# baseboardV0_1Part1.net
KiCad netlist of a schematic drawn in Altium Designer
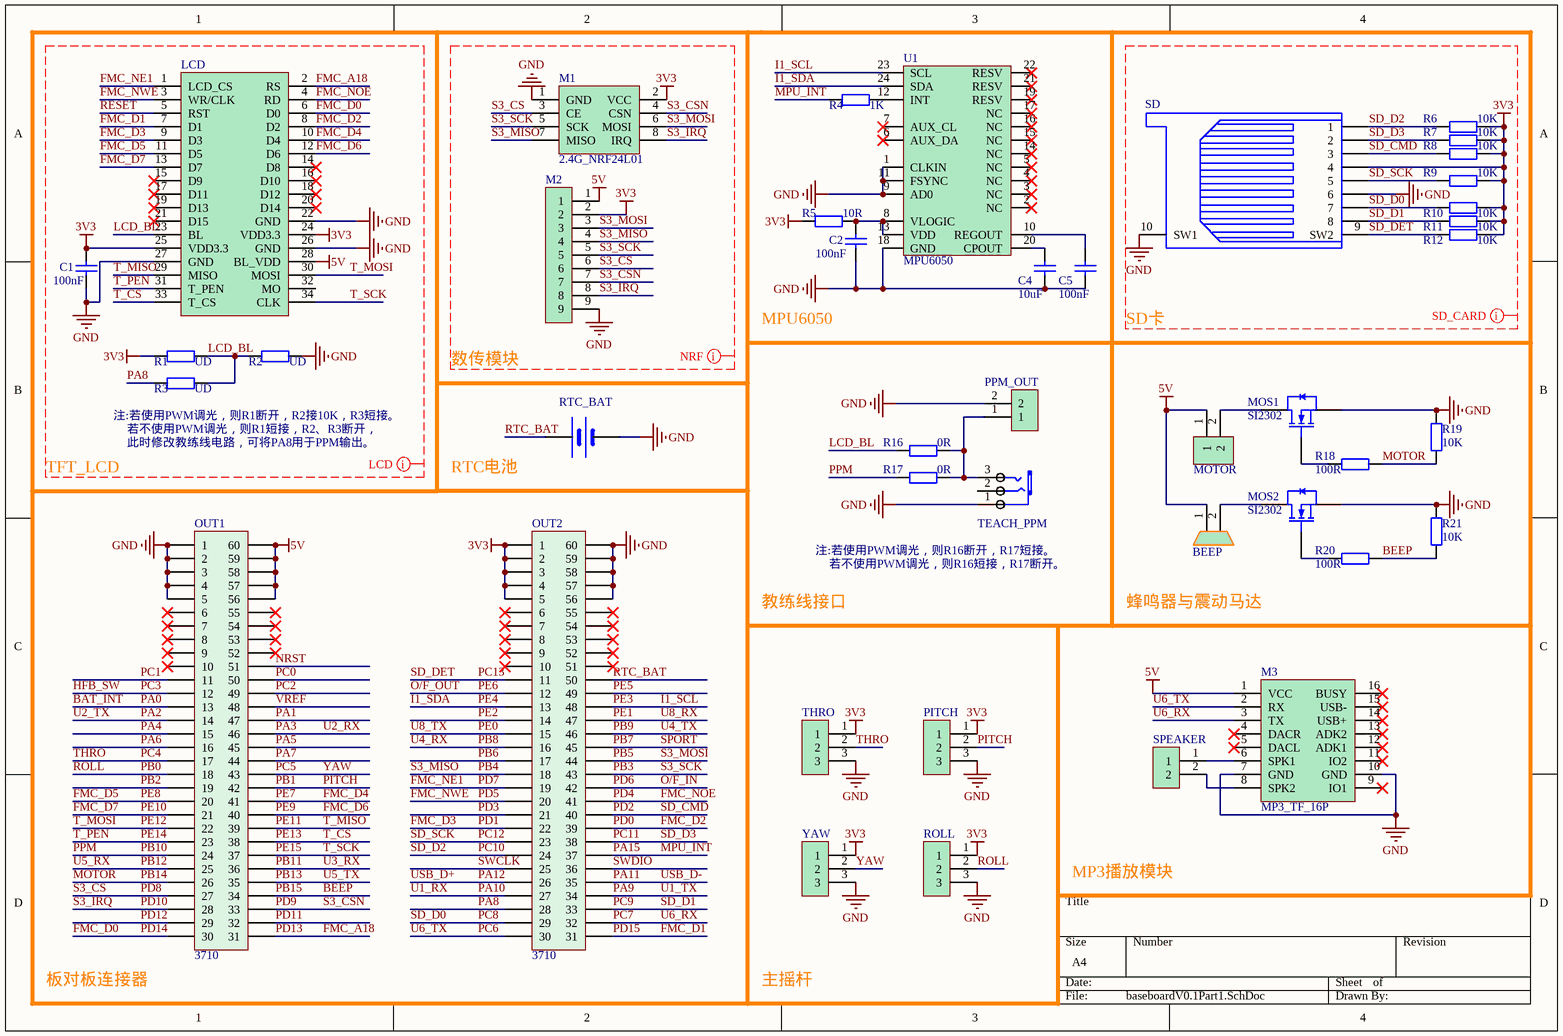
[diagram p0: baseboardV0.1Part1.SchDoc]

(export (version "E")
  (design (tool "Eeschema 10.0.6"))
  (components
    (comp (ref "BEEP")
      (value "BEEP_5020_SMT")
      (footprint "BEEP_5020_SMT")
      (libsource (lib "MT_Device") (part "BEEP_5020_SMT"))
    )
    (comp (ref "C1") (value "100nF") (footprint "0603_C") (libsource (lib "MT_Device") (part "0603_CAP")))
    (comp (ref "C2") (value "100nF") (footprint "0603_C") (libsource (lib "MT_Device") (part "0603_CAP")))
    (comp (ref "C4") (value "10uF") (footprint "0603_C") (libsource (lib "MT_Device") (part "0603_CAP")))
    (comp (ref "C5") (value "100nF") (footprint "0603_C") (libsource (lib "MT_Device") (part "0603_CAP")))
    (comp (ref "LCD")
      (value "LCD_3.5_480*320_SMT")
      (footprint "LCD_3.5_480*320_SMT")
      (libsource (lib "MT_Module") (part "LCD_3.5_480*320_SMT"))
    )
    (comp (ref "M1")
      (value "2.4G_NRF24L01")
      (footprint "2.4G_NRF24L01")
      (libsource (lib "MT_Module") (part "2.4G_NRF24L01"))
    )
    (comp (ref "M2")
      (value "SH1.25mm_9P")
      (footprint "SH1.25MM_9P")
      (libsource (lib "MT_Connector") (part "SH1.25mm_9P"))
    )
    (comp (ref "M3")
      (value "MP3_TF_16P")
      (footprint "MP3_TF_16P")
      (libsource (lib "MT_Module") (part "MP3_TF_16P"))
    )
    (comp (ref "MOS1")
      (value "SI2302")
      (footprint "SOT23")
      (libsource (lib "MT_Device") (part "MOSN_SI2302_SOT23"))
    )
    (comp (ref "MOS2")
      (value "SI2302")
      (footprint "SOT23")
      (libsource (lib "MT_Device") (part "MOSN_SI2302_SOT23"))
    )
    (comp (ref "MOTOR")
      (value "SH1.25mm_2P")
      (footprint "SH1.25mm_2P")
      (libsource (lib "") (part "SH1.25mm_2P_1"))
    )
    (comp (ref "OUT1")
      (value "3710")
      (footprint "3710F060046G3FT01")
      (libsource (lib "MT_Connector") (part "3710F_30*2pin"))
    )
    (comp (ref "OUT2")
      (value "3710")
      (footprint "3710F060046G3FT01")
      (libsource (lib "MT_Connector") (part "3710F_30*2pin"))
    )
    (comp (ref "PITCH")
      (value "pitch")
      (footprint "SH1.25mm_3P")
      (libsource (lib "MT_Connector") (part "SH1.25mm_3P"))
    )
    (comp (ref "PPM_OUT")
      (value "SH1.25mm_2P")
      (footprint "SH1.25mm_2P")
      (libsource (lib "") (part "SH1.25mm_2P_2"))
    )
    (comp (ref "R1") (value "UD") (footprint "0603_R") (libsource (lib "") (part "0603_RES_1")))
    (comp (ref "R2") (value "UD") (footprint "0603_R") (libsource (lib "") (part "0603_RES_1")))
    (comp (ref "R3") (value "UD") (footprint "0603_R") (libsource (lib "") (part "0603_RES_1")))
    (comp (ref "R4") (value "1K") (footprint "0603_R") (libsource (lib "") (part "0603_RES_1")))
    (comp (ref "R5") (value "10R") (footprint "0603_R") (libsource (lib "") (part "0603_RES_1")))
    (comp (ref "R6") (value "10K") (footprint "0603_R") (libsource (lib "") (part "0603_RES_1")))
    (comp (ref "R7") (value "10K") (footprint "0603_R") (libsource (lib "") (part "0603_RES_1")))
    (comp (ref "R8") (value "10K") (footprint "0603_R") (libsource (lib "") (part "0603_RES_1")))
    (comp (ref "R9") (value "10K") (footprint "0603_R") (libsource (lib "") (part "0603_RES_1")))
    (comp (ref "R10") (value "10K") (footprint "0603_R") (libsource (lib "") (part "0603_RES_1")))
    (comp (ref "R11") (value "10K") (footprint "0603_R") (libsource (lib "") (part "0603_RES_1")))
    (comp (ref "R12") (value "10K") (footprint "0603_R") (libsource (lib "") (part "0603_RES_1")))
    (comp (ref "R16") (value "0R") (footprint "0603_R") (libsource (lib "MT_Device") (part "0603_RES")))
    (comp (ref "R17") (value "0R") (footprint "0603_R") (libsource (lib "MT_Device") (part "0603_RES")))
    (comp (ref "R18") (value "100R") (footprint "0603_R") (libsource (lib "") (part "0603_RES_1")))
    (comp (ref "R19") (value "10K") (footprint "0603_R") (libsource (lib "") (part "0603_RES_2")))
    (comp (ref "R20") (value "100R") (footprint "0603_R") (libsource (lib "") (part "0603_RES_1")))
    (comp (ref "R21") (value "10K") (footprint "0603_R") (libsource (lib "") (part "0603_RES_2")))
    (comp (ref "ROLL")
      (value "roll")
      (footprint "SH1.25mm_3P")
      (libsource (lib "MT_Connector") (part "SH1.25mm_3P"))
    )
    (comp (ref "RTC_BAT")
      (value "CR1220_BATTERY")
      (footprint "CR1220_BATTERY")
      (libsource (lib "MT_Device") (part "CR1220_BATTERY"))
    )
    (comp (ref "SD") (value "TF_Card") (footprint "TF_card") (libsource (lib "MT_Device") (part "TF_Card")))
    (comp (ref "SPEAKER")
      (value "SH1.25mm_2P")
      (footprint "SH1.25mm_2P")
      (libsource (lib "MT_Connector") (part "SH1.25mm_2P"))
    )
    (comp (ref "TEACH_PPM")
      (value "AUDIO_PJ313D")
      (footprint "AUDIO_PJ313D")
      (libsource (lib "MT_Device") (part "AUDIO_PJ313D"))
    )
    (comp (ref "THRO")
      (value "thro")
      (footprint "SH1.25mm_3P")
      (libsource (lib "MT_Connector") (part "SH1.25mm_3P"))
    )
    (comp (ref "U1") (value "MPU6050") (footprint "QFN24") (libsource (lib "MT_Chip") (part "MPU6050")))
    (comp (ref "YAW")
      (value "yaw")
      (footprint "SH1.25mm_3P")
      (libsource (lib "MT_Connector") (part "SH1.25mm_3P"))
    )
  )
  (nets
    (net (code "1") (name "/BAT_INT") (class "Default")
      (node (ref "OUT1") (pin "13") (pinfunction "13_13") (pintype "passive"))
    )
    (net (code "2") (name "/BEEP") (class "Default")
      (node (ref "OUT1") (pin "34") (pinfunction "34_34") (pintype "passive"))
      (node (ref "R20") (pin "2") (pinfunction "2_2") (pintype "passive"))
      (node (ref "R21") (pin "1") (pinfunction "1_1") (pintype "passive"))
    )
    (net (code "3") (name "/FMC_A18") (class "Default")
      (node (ref "LCD") (pin "2") (pinfunction "RS_2") (pintype "passive"))
      (node (ref "OUT1") (pin "31") (pinfunction "31_31") (pintype "passive"))
    )
    (net (code "4") (name "/FMC_D0") (class "Default")
      (node (ref "LCD") (pin "6") (pinfunction "D0_6") (pintype "passive"))
      (node (ref "OUT1") (pin "30") (pinfunction "30_30") (pintype "passive"))
    )
    (net (code "5") (name "/FMC_D1") (class "Default")
      (node (ref "LCD") (pin "7") (pinfunction "D1_7") (pintype "passive"))
      (node (ref "OUT2") (pin "31") (pinfunction "31_31") (pintype "passive"))
    )
    (net (code "6") (name "/FMC_D2") (class "Default")
      (node (ref "LCD") (pin "8") (pinfunction "D2_8") (pintype "passive"))
      (node (ref "OUT2") (pin "39") (pinfunction "39_39") (pintype "passive"))
    )
    (net (code "7") (name "/FMC_D3") (class "Default")
      (node (ref "LCD") (pin "9") (pinfunction "D3_9") (pintype "passive"))
      (node (ref "OUT2") (pin "22") (pinfunction "22_22") (pintype "passive"))
    )
    (net (code "8") (name "/FMC_D4") (class "Default")
      (node (ref "LCD") (pin "10") (pinfunction "D4_10") (pintype "passive"))
      (node (ref "OUT1") (pin "41") (pinfunction "41_41") (pintype "passive"))
    )
    (net (code "9") (name "/FMC_D5") (class "Default")
      (node (ref "LCD") (pin "11") (pinfunction "D5_11") (pintype "passive"))
      (node (ref "OUT1") (pin "20") (pinfunction "20_20") (pintype "passive"))
    )
    (net (code "10") (name "/FMC_D6") (class "Default")
      (node (ref "LCD") (pin "12") (pinfunction "D6_12") (pintype "passive"))
      (node (ref "OUT1") (pin "40") (pinfunction "40_40") (pintype "passive"))
    )
    (net (code "11") (name "/FMC_D7") (class "Default")
      (node (ref "LCD") (pin "13") (pinfunction "D7_13") (pintype "passive"))
      (node (ref "OUT1") (pin "21") (pinfunction "21_21") (pintype "passive"))
    )
    (net (code "12") (name "/FMC_NE1") (class "Default")
      (node (ref "LCD") (pin "1") (pinfunction "LCD_CS_1") (pintype "passive"))
      (node (ref "OUT2") (pin "19") (pinfunction "19_19") (pintype "passive"))
    )
    (net (code "13") (name "/FMC_NOE") (class "Default")
      (node (ref "LCD") (pin "4") (pinfunction "RD_4") (pintype "passive"))
      (node (ref "OUT2") (pin "41") (pinfunction "41_41") (pintype "passive"))
    )
    (net (code "14") (name "/FMC_NWE") (class "Default")
      (node (ref "LCD") (pin "3") (pinfunction "WR/CLK_3") (pintype "passive"))
      (node (ref "OUT2") (pin "20") (pinfunction "20_20") (pintype "passive"))
    )
    (net (code "15") (name "/HFB_SW") (class "Default")
      (node (ref "OUT1") (pin "12") (pinfunction "12_12") (pintype "passive"))
    )
    (net (code "16") (name "/I1_SCL") (class "Default")
      (node (ref "OUT2") (pin "48") (pinfunction "48_48") (pintype "passive"))
      (node (ref "U1") (pin "23") (pinfunction "SCL_23") (pintype "passive"))
    )
    (net (code "17") (name "/I1_SDA") (class "Default")
      (node (ref "OUT2") (pin "13") (pinfunction "13_13") (pintype "passive"))
      (node (ref "U1") (pin "24") (pinfunction "SDA_24") (pintype "passive"))
    )
    (net (code "18") (name "/LCD_BL") (class "Default")
      (node (ref "LCD") (pin "23") (pinfunction "BL_23") (pintype "passive"))
      (node (ref "R1") (pin "2") (pinfunction "2_2") (pintype "passive"))
      (node (ref "R16") (pin "2") (pinfunction "2_2") (pintype "passive"))
      (node (ref "R2") (pin "1") (pinfunction "1_1") (pintype "passive"))
      (node (ref "R3") (pin "2") (pinfunction "2_2") (pintype "passive"))
    )
    (net (code "19") (name "/MOTOR") (class "Default")
      (node (ref "OUT1") (pin "26") (pinfunction "26_26") (pintype "passive"))
      (node (ref "R18") (pin "2") (pinfunction "2_2") (pintype "passive"))
      (node (ref "R19") (pin "1") (pinfunction "1_1") (pintype "passive"))
    )
    (net (code "20") (name "/MPU_INT") (class "Default")
      (node (ref "OUT2") (pin "37") (pinfunction "37_37") (pintype "passive"))
      (node (ref "R4") (pin "1") (pinfunction "1_1") (pintype "passive"))
    )
    (net (code "21") (name "/NRST") (class "Default")
      (node (ref "OUT1") (pin "51") (pinfunction "51_51") (pintype "passive"))
    )
    (net (code "22") (name "/O{slash}F_IN") (class "Default")
      (node (ref "OUT2") (pin "42") (pinfunction "42_42") (pintype "passive"))
    )
    (net (code "23") (name "/O{slash}F_OUT") (class "Default")
      (node (ref "OUT2") (pin "12") (pinfunction "12_12") (pintype "passive"))
    )
    (net (code "24") (name "/PA1") (class "Default")
      (node (ref "OUT1") (pin "47") (pinfunction "47_47") (pintype "passive"))
    )
    (net (code "25") (name "/PA2") (class "Default")
      (node (ref "OUT1") (pin "14") (pinfunction "14_14") (pintype "passive"))
    )
    (net (code "26") (name "/PA3") (class "Default")
      (node (ref "OUT1") (pin "46") (pinfunction "46_46") (pintype "passive"))
    )
    (net (code "27") (name "/PA4") (class "Default")
      (node (ref "OUT1") (pin "15") (pinfunction "15_15") (pintype "passive"))
    )
    (net (code "28") (name "/PA5") (class "Default")
      (node (ref "OUT1") (pin "45") (pinfunction "45_45") (pintype "passive"))
    )
    (net (code "29") (name "/PA6") (class "Default")
      (node (ref "OUT1") (pin "16") (pinfunction "16_16") (pintype "passive"))
    )
    (net (code "30") (name "/PA7") (class "Default")
      (node (ref "OUT1") (pin "44") (pinfunction "44_44") (pintype "passive"))
    )
    (net (code "31") (name "/PA8") (class "Default")
      (node (ref "OUT2") (pin "28") (pinfunction "28_28") (pintype "passive"))
      (node (ref "R3") (pin "1") (pinfunction "1_1") (pintype "passive"))
    )
    (net (code "32") (name "/PA9") (class "Default")
      (node (ref "OUT2") (pin "34") (pinfunction "34_34") (pintype "passive"))
    )
    (net (code "33") (name "/PA10") (class "Default")
      (node (ref "OUT2") (pin "27") (pinfunction "27_27") (pintype "passive"))
    )
    (net (code "34") (name "/PA11") (class "Default")
      (node (ref "OUT2") (pin "35") (pinfunction "35_35") (pintype "passive"))
    )
    (net (code "35") (name "/PA12") (class "Default")
      (node (ref "OUT2") (pin "26") (pinfunction "26_26") (pintype "passive"))
    )
    (net (code "36") (name "/PB0") (class "Default")
      (node (ref "OUT1") (pin "18") (pinfunction "18_18") (pintype "passive"))
      (node (ref "ROLL") (pin "2") (pinfunction "2_2") (pintype "passive"))
    )
    (net (code "37") (name "/PB1") (class "Default")
      (node (ref "OUT1") (pin "42") (pinfunction "42_42") (pintype "passive"))
      (node (ref "PITCH") (pin "2") (pinfunction "2_2") (pintype "passive"))
    )
    (net (code "38") (name "/PB2") (class "Default")
      (node (ref "OUT1") (pin "19") (pinfunction "19_19") (pintype "passive"))
    )
    (net (code "39") (name "/PB3") (class "Default")
      (node (ref "M1") (pin "5") (pinfunction "SCK_5") (pintype "passive"))
      (node (ref "M2") (pin "5") (pinfunction "5_5") (pintype "passive"))
      (node (ref "OUT2") (pin "43") (pinfunction "43_43") (pintype "passive"))
    )
    (net (code "40") (name "/PB4") (class "Default")
      (node (ref "M1") (pin "7") (pinfunction "MISO_7") (pintype "passive"))
      (node (ref "M2") (pin "4") (pinfunction "4_4") (pintype "passive"))
      (node (ref "OUT2") (pin "18") (pinfunction "18_18") (pintype "passive"))
    )
    (net (code "41") (name "/PB5") (class "Default")
      (node (ref "M1") (pin "6") (pinfunction "MOSI_6") (pintype "passive"))
      (node (ref "M2") (pin "3") (pinfunction "3_3") (pintype "passive"))
      (node (ref "OUT2") (pin "44") (pinfunction "44_44") (pintype "passive"))
    )
    (net (code "42") (name "/PB6") (class "Default")
      (node (ref "OUT2") (pin "17") (pinfunction "17_17") (pintype "passive"))
    )
    (net (code "43") (name "/PB7") (class "Default")
      (node (ref "OUT2") (pin "45") (pinfunction "45_45") (pintype "passive"))
    )
    (net (code "44") (name "/PB8") (class "Default")
      (node (ref "OUT2") (pin "16") (pinfunction "16_16") (pintype "passive"))
    )
    (net (code "45") (name "/PB9") (class "Default")
      (node (ref "OUT2") (pin "46") (pinfunction "46_46") (pintype "passive"))
    )
    (net (code "46") (name "/PB10") (class "Default")
      (node (ref "OUT1") (pin "24") (pinfunction "24_24") (pintype "passive"))
      (node (ref "R17") (pin "2") (pinfunction "2_2") (pintype "passive"))
    )
    (net (code "47") (name "/PB11") (class "Default")
      (node (ref "OUT1") (pin "36") (pinfunction "36_36") (pintype "passive"))
    )
    (net (code "48") (name "/PB12") (class "Default")
      (node (ref "OUT1") (pin "25") (pinfunction "25_25") (pintype "passive"))
    )
    (net (code "49") (name "/PB13") (class "Default")
      (node (ref "OUT1") (pin "35") (pinfunction "35_35") (pintype "passive"))
    )
    (net (code "50") (name "/PC0") (class "Default")
      (node (ref "OUT1") (pin "50") (pinfunction "50_50") (pintype "passive"))
    )
    (net (code "51") (name "/PC1") (class "Default")
      (node (ref "OUT1") (pin "11") (pinfunction "11_11") (pintype "passive"))
    )
    (net (code "52") (name "/PC2") (class "Default")
      (node (ref "OUT1") (pin "49") (pinfunction "49_49") (pintype "passive"))
    )
    (net (code "53") (name "/PC4") (class "Default")
      (node (ref "OUT1") (pin "17") (pinfunction "17_17") (pintype "passive"))
      (node (ref "THRO") (pin "2") (pinfunction "2_2") (pintype "passive"))
    )
    (net (code "54") (name "/PC5") (class "Default")
      (node (ref "OUT1") (pin "43") (pinfunction "43_43") (pintype "passive"))
      (node (ref "YAW") (pin "2") (pinfunction "2_2") (pintype "passive"))
    )
    (net (code "55") (name "/PC6") (class "Default")
      (node (ref "M3") (pin "2") (pinfunction "RX_2") (pintype "passive"))
      (node (ref "OUT2") (pin "30") (pinfunction "30_30") (pintype "passive"))
    )
    (net (code "56") (name "/PC7") (class "Default")
      (node (ref "M3") (pin "3") (pinfunction "TX_3") (pintype "passive"))
      (node (ref "OUT2") (pin "32") (pinfunction "32_32") (pintype "passive"))
    )
    (net (code "57") (name "/PC8") (class "Default")
      (node (ref "OUT2") (pin "29") (pinfunction "29_29") (pintype "passive"))
      (node (ref "R10") (pin "1") (pinfunction "1_1") (pintype "passive"))
      (node (ref "SD") (pin "7") (pinfunction "7_7") (pintype "passive"))
    )
    (net (code "58") (name "/PC9") (class "Default")
      (node (ref "OUT2") (pin "33") (pinfunction "33_33") (pintype "passive"))
      (node (ref "R11") (pin "1") (pinfunction "1_1") (pintype "passive"))
      (node (ref "SD") (pin "8") (pinfunction "8_8") (pintype "passive"))
    )
    (net (code "59") (name "/PC10") (class "Default")
      (node (ref "OUT2") (pin "24") (pinfunction "24_24") (pintype "passive"))
      (node (ref "R6") (pin "1") (pinfunction "1_1") (pintype "passive"))
      (node (ref "SD") (pin "1") (pinfunction "1_1") (pintype "passive"))
    )
    (net (code "60") (name "/PC11") (class "Default")
      (node (ref "OUT2") (pin "38") (pinfunction "38_38") (pintype "passive"))
      (node (ref "R7") (pin "1") (pinfunction "1_1") (pintype "passive"))
      (node (ref "SD") (pin "2") (pinfunction "2_2") (pintype "passive"))
    )
    (net (code "61") (name "/PC12") (class "Default")
      (node (ref "OUT2") (pin "23") (pinfunction "23_23") (pintype "passive"))
      (node (ref "R9") (pin "1") (pinfunction "1_1") (pintype "passive"))
      (node (ref "SD") (pin "5") (pinfunction "5_5") (pintype "passive"))
    )
    (net (code "62") (name "/PC13") (class "Default")
      (node (ref "OUT2") (pin "11") (pinfunction "11_11") (pintype "passive"))
      (node (ref "R12") (pin "1") (pinfunction "1_1") (pintype "passive"))
      (node (ref "SD") (pin "9") (pinfunction "SW2_9") (pintype "passive"))
    )
    (net (code "63") (name "/PD2") (class "Default")
      (node (ref "OUT2") (pin "40") (pinfunction "40_40") (pintype "passive"))
      (node (ref "R8") (pin "1") (pinfunction "1_1") (pintype "passive"))
      (node (ref "SD") (pin "3") (pinfunction "3_3") (pintype "passive"))
    )
    (net (code "64") (name "/PD3") (class "Default")
      (node (ref "OUT2") (pin "21") (pinfunction "21_21") (pintype "passive"))
    )
    (net (code "65") (name "/PD8") (class "Default")
      (node (ref "M1") (pin "3") (pinfunction "CE_3") (pintype "passive"))
      (node (ref "M2") (pin "6") (pinfunction "6_6") (pintype "passive"))
      (node (ref "OUT1") (pin "27") (pinfunction "27_27") (pintype "passive"))
    )
    (net (code "66") (name "/PD9") (class "Default")
      (node (ref "M1") (pin "4") (pinfunction "CSN_4") (pintype "passive"))
      (node (ref "M2") (pin "7") (pinfunction "7_7") (pintype "passive"))
      (node (ref "OUT1") (pin "33") (pinfunction "33_33") (pintype "passive"))
    )
    (net (code "67") (name "/PD10") (class "Default")
      (node (ref "M1") (pin "8") (pinfunction "IRQ_8") (pintype "passive"))
      (node (ref "M2") (pin "8") (pinfunction "8_8") (pintype "passive"))
      (node (ref "OUT1") (pin "28") (pinfunction "28_28") (pintype "passive"))
    )
    (net (code "68") (name "/PD11") (class "Default")
      (node (ref "OUT1") (pin "32") (pinfunction "32_32") (pintype "passive"))
    )
    (net (code "69") (name "/PD12") (class "Default")
      (node (ref "OUT1") (pin "29") (pinfunction "29_29") (pintype "passive"))
    )
    (net (code "70") (name "/PE0") (class "Default")
      (node (ref "OUT2") (pin "15") (pinfunction "15_15") (pintype "passive"))
    )
    (net (code "71") (name "/PE1") (class "Default")
      (node (ref "OUT2") (pin "47") (pinfunction "47_47") (pintype "passive"))
    )
    (net (code "72") (name "/PE2") (class "Default")
      (node (ref "OUT2") (pin "14") (pinfunction "14_14") (pintype "passive"))
    )
    (net (code "73") (name "/PE5") (class "Default")
      (node (ref "OUT2") (pin "49") (pinfunction "49_49") (pintype "passive"))
    )
    (net (code "74") (name "/PE11") (class "Default")
      (node (ref "LCD") (pin "29") (pinfunction "MISO_29") (pintype "passive"))
      (node (ref "OUT1") (pin "39") (pinfunction "39_39") (pintype "passive"))
    )
    (net (code "75") (name "/PE12") (class "Default")
      (node (ref "LCD") (pin "30") (pinfunction "MOSI_30") (pintype "passive"))
      (node (ref "OUT1") (pin "22") (pinfunction "22_22") (pintype "passive"))
    )
    (net (code "76") (name "/PE13") (class "Default")
      (node (ref "LCD") (pin "33") (pinfunction "T_CS_33") (pintype "passive"))
      (node (ref "OUT1") (pin "38") (pinfunction "38_38") (pintype "passive"))
    )
    (net (code "77") (name "/PE14") (class "Default")
      (node (ref "LCD") (pin "31") (pinfunction "T_PEN_31") (pintype "passive"))
      (node (ref "OUT1") (pin "23") (pinfunction "23_23") (pintype "passive"))
    )
    (net (code "78") (name "/PE15") (class "Default")
      (node (ref "LCD") (pin "34") (pinfunction "CLK_34") (pintype "passive"))
      (node (ref "OUT1") (pin "37") (pinfunction "37_37") (pintype "passive"))
    )
    (net (code "79") (name "/RESET") (class "Default")
      (node (ref "LCD") (pin "5") (pinfunction "RST_5") (pintype "passive"))
    )
    (net (code "80") (name "/RTC_BAT") (class "Default")
      (node (ref "OUT2") (pin "50") (pinfunction "50_50") (pintype "passive"))
      (node (ref "RTC_BAT") (pin "1") (pinfunction "VCC_1") (pintype "passive"))
    )
    (net (code "81") (name "/SWCLK") (class "Default")
      (node (ref "OUT2") (pin "25") (pinfunction "25_25") (pintype "passive"))
    )
    (net (code "82") (name "/SWDIO") (class "Default")
      (node (ref "OUT2") (pin "36") (pinfunction "36_36") (pintype "passive"))
    )
    (net (code "83") (name "/VREF") (class "Default")
      (node (ref "OUT1") (pin "48") (pinfunction "48_48") (pintype "passive"))
    )
    (net (code "84") (name "3V3") (class "Default")
      (node (ref "C1") (pin "2") (pinfunction "2_2") (pintype "passive"))
      (node (ref "LCD") (pin "24") (pinfunction "VDD3.3_24") (pintype "passive"))
      (node (ref "LCD") (pin "25") (pinfunction "VDD3.3_25") (pintype "passive"))
      (node (ref "M1") (pin "2") (pinfunction "VCC_2") (pintype "passive"))
      (node (ref "M2") (pin "2") (pinfunction "2_2") (pintype "passive"))
      (node (ref "OUT2") (pin "1") (pinfunction "1_1") (pintype "passive"))
      (node (ref "OUT2") (pin "2") (pinfunction "2_2") (pintype "passive"))
      (node (ref "OUT2") (pin "3") (pinfunction "3_3") (pintype "passive"))
      (node (ref "OUT2") (pin "4") (pinfunction "4_4") (pintype "passive"))
      (node (ref "OUT2") (pin "5") (pinfunction "5_5") (pintype "passive"))
      (node (ref "PITCH") (pin "1") (pinfunction "1_1") (pintype "passive"))
      (node (ref "R1") (pin "1") (pinfunction "1_1") (pintype "passive"))
      (node (ref "R10") (pin "2") (pinfunction "2_2") (pintype "passive"))
      (node (ref "R11") (pin "2") (pinfunction "2_2") (pintype "passive"))
      (node (ref "R12") (pin "2") (pinfunction "2_2") (pintype "passive"))
      (node (ref "R5") (pin "1") (pinfunction "1_1") (pintype "passive"))
      (node (ref "R6") (pin "2") (pinfunction "2_2") (pintype "passive"))
      (node (ref "R7") (pin "2") (pinfunction "2_2") (pintype "passive"))
      (node (ref "R8") (pin "2") (pinfunction "2_2") (pintype "passive"))
      (node (ref "R9") (pin "2") (pinfunction "2_2") (pintype "passive"))
      (node (ref "ROLL") (pin "1") (pinfunction "1_1") (pintype "passive"))
      (node (ref "SD") (pin "4") (pinfunction "4_4") (pintype "passive"))
      (node (ref "THRO") (pin "1") (pinfunction "1_1") (pintype "passive"))
      (node (ref "YAW") (pin "1") (pinfunction "1_1") (pintype "passive"))
    )
    (net (code "85") (name "5V") (class "Default")
      (node (ref "BEEP") (pin "1") (pinfunction "1_1") (pintype "passive"))
      (node (ref "LCD") (pin "28") (pinfunction "BL_VDD_28") (pintype "passive"))
      (node (ref "M2") (pin "1") (pinfunction "1_1") (pintype "passive"))
      (node (ref "M3") (pin "1") (pinfunction "VCC_1") (pintype "passive"))
      (node (ref "MOTOR") (pin "1") (pinfunction "1_1") (pintype "passive"))
      (node (ref "OUT1") (pin "56") (pinfunction "56_56") (pintype "passive"))
      (node (ref "OUT1") (pin "57") (pinfunction "57_57") (pintype "passive"))
      (node (ref "OUT1") (pin "58") (pinfunction "58_58") (pintype "passive"))
      (node (ref "OUT1") (pin "59") (pinfunction "59_59") (pintype "passive"))
      (node (ref "OUT1") (pin "60") (pinfunction "60_60") (pintype "passive"))
    )
    (net (code "86") (name "GND") (class "Default")
      (node (ref "C1") (pin "1") (pinfunction "1_1") (pintype "passive"))
      (node (ref "C2") (pin "1") (pinfunction "1_1") (pintype "passive"))
      (node (ref "C4") (pin "2") (pinfunction "2_2") (pintype "passive"))
      (node (ref "C5") (pin "2") (pinfunction "2_2") (pintype "passive"))
      (node (ref "LCD") (pin "22") (pinfunction "GND_22") (pintype "passive"))
      (node (ref "LCD") (pin "26") (pinfunction "GND_26") (pintype "passive"))
      (node (ref "LCD") (pin "27") (pinfunction "GND_27") (pintype "passive"))
      (node (ref "M1") (pin "1") (pinfunction "GND_1") (pintype "passive"))
      (node (ref "M2") (pin "9") (pinfunction "9_9") (pintype "passive"))
      (node (ref "M3") (pin "10") (pinfunction "GND_10") (pintype "passive"))
      (node (ref "M3") (pin "7") (pinfunction "GND_7") (pintype "passive"))
      (node (ref "MOS1") (pin "2") (pinfunction "S_2") (pintype "passive"))
      (node (ref "MOS2") (pin "2") (pinfunction "S_2") (pintype "passive"))
      (node (ref "OUT1") (pin "1") (pinfunction "1_1") (pintype "passive"))
      (node (ref "OUT1") (pin "2") (pinfunction "2_2") (pintype "passive"))
      (node (ref "OUT1") (pin "3") (pinfunction "3_3") (pintype "passive"))
      (node (ref "OUT1") (pin "4") (pinfunction "4_4") (pintype "passive"))
      (node (ref "OUT1") (pin "5") (pinfunction "5_5") (pintype "passive"))
      (node (ref "OUT2") (pin "56") (pinfunction "56_56") (pintype "passive"))
      (node (ref "OUT2") (pin "57") (pinfunction "57_57") (pintype "passive"))
      (node (ref "OUT2") (pin "58") (pinfunction "58_58") (pintype "passive"))
      (node (ref "OUT2") (pin "59") (pinfunction "59_59") (pintype "passive"))
      (node (ref "OUT2") (pin "60") (pinfunction "60_60") (pintype "passive"))
      (node (ref "PITCH") (pin "3") (pinfunction "3_3") (pintype "passive"))
      (node (ref "PPM_OUT") (pin "2") (pinfunction "2_2") (pintype "passive"))
      (node (ref "R19") (pin "2") (pinfunction "2_2") (pintype "passive"))
      (node (ref "R2") (pin "2") (pinfunction "2_2") (pintype "passive"))
      (node (ref "R21") (pin "2") (pinfunction "2_2") (pintype "passive"))
      (node (ref "ROLL") (pin "3") (pinfunction "3_3") (pintype "passive"))
      (node (ref "RTC_BAT") (pin "2") (pinfunction "GND_2") (pintype "passive"))
      (node (ref "SD") (pin "10") (pinfunction "SW1_10") (pintype "passive"))
      (node (ref "SD") (pin "6") (pinfunction "6_6") (pintype "passive"))
      (node (ref "TEACH_PPM") (pin "1") (pinfunction "COM_1") (pintype "passive"))
      (node (ref "THRO") (pin "3") (pinfunction "3_3") (pintype "passive"))
      (node (ref "U1") (pin "1") (pinfunction "CLKIN_1") (pintype "passive"))
      (node (ref "U1") (pin "11") (pinfunction "FSYNC_11") (pintype "passive"))
      (node (ref "U1") (pin "18") (pinfunction "GND_18") (pintype "passive"))
      (node (ref "U1") (pin "9") (pinfunction "AD0_9") (pintype "passive"))
      (node (ref "YAW") (pin "3") (pinfunction "3_3") (pintype "passive"))
    )
    (net (code "87") (name "Net-(M3-SPK1)") (class "Default")
      (node (ref "M3") (pin "6") (pinfunction "SPK1_6") (pintype "passive"))
      (node (ref "SPEAKER") (pin "1") (pinfunction "1_1") (pintype "passive"))
    )
    (net (code "88") (name "Net-(M3-SPK2)") (class "Default")
      (node (ref "M3") (pin "8") (pinfunction "SPK2_8") (pintype "passive"))
      (node (ref "SPEAKER") (pin "2") (pinfunction "2_2") (pintype "passive"))
    )
    (net (code "89") (name "Net-(MOS1-D)") (class "Default")
      (node (ref "MOS1") (pin "3") (pinfunction "D_3") (pintype "passive"))
      (node (ref "MOTOR") (pin "2") (pinfunction "2_2") (pintype "passive"))
    )
    (net (code "90") (name "Net-(MOS1-G)") (class "Default")
      (node (ref "MOS1") (pin "1") (pinfunction "G_1") (pintype "passive"))
      (node (ref "R18") (pin "1") (pinfunction "1_1") (pintype "passive"))
    )
    (net (code "91") (name "Net-(MOS2-D)") (class "Default")
      (node (ref "BEEP") (pin "2") (pinfunction "2_2") (pintype "passive"))
      (node (ref "MOS2") (pin "3") (pinfunction "D_3") (pintype "passive"))
    )
    (net (code "92") (name "Net-(MOS2-G)") (class "Default")
      (node (ref "MOS2") (pin "1") (pinfunction "G_1") (pintype "passive"))
      (node (ref "R20") (pin "1") (pinfunction "1_1") (pintype "passive"))
    )
    (net (code "93") (name "Net-(TEACH_PPM-CHL)") (class "Default")
      (node (ref "PPM_OUT") (pin "1") (pinfunction "1_1") (pintype "passive"))
      (node (ref "R16") (pin "1") (pinfunction "1_1") (pintype "passive"))
      (node (ref "R17") (pin "1") (pinfunction "1_1") (pintype "passive"))
      (node (ref "TEACH_PPM") (pin "3") (pinfunction "CHL_3") (pintype "passive"))
    )
    (net (code "94") (name "Net-(U1-CPOUT)") (class "Default")
      (node (ref "C4") (pin "1") (pinfunction "1_1") (pintype "passive"))
      (node (ref "U1") (pin "20") (pinfunction "CPOUT_20") (pintype "passive"))
    )
    (net (code "95") (name "Net-(U1-INT)") (class "Default")
      (node (ref "R4") (pin "2") (pinfunction "2_2") (pintype "passive"))
      (node (ref "U1") (pin "12") (pinfunction "INT_12") (pintype "passive"))
    )
    (net (code "96") (name "Net-(U1-REGOUT)") (class "Default")
      (node (ref "C5") (pin "1") (pinfunction "1_1") (pintype "passive"))
      (node (ref "U1") (pin "10") (pinfunction "REGOUT_10") (pintype "passive"))
    )
    (net (code "97") (name "Net-(U1-VDD)") (class "Default")
      (node (ref "C2") (pin "2") (pinfunction "2_2") (pintype "passive"))
      (node (ref "R5") (pin "2") (pinfunction "2_2") (pintype "passive"))
      (node (ref "U1") (pin "13") (pinfunction "VDD_13") (pintype "passive"))
      (node (ref "U1") (pin "8") (pinfunction "VLOGIC_8") (pintype "passive"))
    )
    (net (code "98") (name "unconnected-(LCD-D8-Pad14)") (class "Default")
      (node (ref "LCD") (pin "14") (pinfunction "D8_14") (pintype "passive+no_connect"))
    )
    (net (code "99") (name "unconnected-(LCD-D9-Pad15)") (class "Default")
      (node (ref "LCD") (pin "15") (pinfunction "D9_15") (pintype "passive+no_connect"))
    )
    (net (code "100") (name "unconnected-(LCD-D10-Pad16)") (class "Default")
      (node (ref "LCD") (pin "16") (pinfunction "D10_16") (pintype "passive+no_connect"))
    )
    (net (code "101") (name "unconnected-(LCD-D11-Pad17)") (class "Default")
      (node (ref "LCD") (pin "17") (pinfunction "D11_17") (pintype "passive+no_connect"))
    )
    (net (code "102") (name "unconnected-(LCD-D12-Pad18)") (class "Default")
      (node (ref "LCD") (pin "18") (pinfunction "D12_18") (pintype "passive+no_connect"))
    )
    (net (code "103") (name "unconnected-(LCD-D13-Pad19)") (class "Default")
      (node (ref "LCD") (pin "19") (pinfunction "D13_19") (pintype "passive+no_connect"))
    )
    (net (code "104") (name "unconnected-(LCD-D14-Pad20)") (class "Default")
      (node (ref "LCD") (pin "20") (pinfunction "D14_20") (pintype "passive+no_connect"))
    )
    (net (code "105") (name "unconnected-(LCD-D15-Pad21)") (class "Default")
      (node (ref "LCD") (pin "21") (pinfunction "D15_21") (pintype "passive+no_connect"))
    )
    (net (code "106") (name "unconnected-(LCD-MO-Pad32)") (class "Default")
      (node (ref "LCD") (pin "32") (pinfunction "MO_32") (pintype "passive"))
    )
    (net (code "107") (name "unconnected-(M3-ADK1-Pad12)") (class "Default")
      (node (ref "M3") (pin "12") (pinfunction "ADK1_12") (pintype "passive+no_connect"))
    )
    (net (code "108") (name "unconnected-(M3-ADK2-Pad13)") (class "Default")
      (node (ref "M3") (pin "13") (pinfunction "ADK2_13") (pintype "passive+no_connect"))
    )
    (net (code "109") (name "unconnected-(M3-BUSY-Pad16)") (class "Default")
      (node (ref "M3") (pin "16") (pinfunction "BUSY_16") (pintype "passive+no_connect"))
    )
    (net (code "110") (name "unconnected-(M3-DACL-Pad5)") (class "Default")
      (node (ref "M3") (pin "5") (pinfunction "DACL_5") (pintype "passive+no_connect"))
    )
    (net (code "111") (name "unconnected-(M3-DACR-Pad4)") (class "Default")
      (node (ref "M3") (pin "4") (pinfunction "DACR_4") (pintype "passive+no_connect"))
    )
    (net (code "112") (name "unconnected-(M3-IO1-Pad9)") (class "Default")
      (node (ref "M3") (pin "9") (pinfunction "IO1_9") (pintype "passive+no_connect"))
    )
    (net (code "113") (name "unconnected-(M3-IO2-Pad11)") (class "Default")
      (node (ref "M3") (pin "11") (pinfunction "IO2_11") (pintype "passive+no_connect"))
    )
    (net (code "114") (name "unconnected-(M3-USB+-Pad14)") (class "Default")
      (node (ref "M3") (pin "14") (pinfunction "USB+_14") (pintype "passive+no_connect"))
    )
    (net (code "115") (name "unconnected-(M3-USB--Pad15)") (class "Default")
      (node (ref "M3") (pin "15") (pinfunction "USB-_15") (pintype "passive+no_connect"))
    )
    (net (code "116") (name "unconnected-(OUT1-Pad6)") (class "Default")
      (node (ref "OUT1") (pin "6") (pinfunction "6_6") (pintype "passive+no_connect"))
    )
    (net (code "117") (name "unconnected-(OUT1-Pad7)") (class "Default")
      (node (ref "OUT1") (pin "7") (pinfunction "7_7") (pintype "passive+no_connect"))
    )
    (net (code "118") (name "unconnected-(OUT1-Pad8)") (class "Default")
      (node (ref "OUT1") (pin "8") (pinfunction "8_8") (pintype "passive+no_connect"))
    )
    (net (code "119") (name "unconnected-(OUT1-Pad9)") (class "Default")
      (node (ref "OUT1") (pin "9") (pinfunction "9_9") (pintype "passive+no_connect"))
    )
    (net (code "120") (name "unconnected-(OUT1-Pad10)") (class "Default")
      (node (ref "OUT1") (pin "10") (pinfunction "10_10") (pintype "passive+no_connect"))
    )
    (net (code "121") (name "unconnected-(OUT1-Pad52)") (class "Default")
      (node (ref "OUT1") (pin "52") (pinfunction "52_52") (pintype "passive+no_connect"))
    )
    (net (code "122") (name "unconnected-(OUT1-Pad53)") (class "Default")
      (node (ref "OUT1") (pin "53") (pinfunction "53_53") (pintype "passive+no_connect"))
    )
    (net (code "123") (name "unconnected-(OUT1-Pad54)") (class "Default")
      (node (ref "OUT1") (pin "54") (pinfunction "54_54") (pintype "passive+no_connect"))
    )
    (net (code "124") (name "unconnected-(OUT1-Pad55)") (class "Default")
      (node (ref "OUT1") (pin "55") (pinfunction "55_55") (pintype "passive+no_connect"))
    )
    (net (code "125") (name "unconnected-(OUT2-Pad6)") (class "Default")
      (node (ref "OUT2") (pin "6") (pinfunction "6_6") (pintype "passive+no_connect"))
    )
    (net (code "126") (name "unconnected-(OUT2-Pad7)") (class "Default")
      (node (ref "OUT2") (pin "7") (pinfunction "7_7") (pintype "passive+no_connect"))
    )
    (net (code "127") (name "unconnected-(OUT2-Pad8)") (class "Default")
      (node (ref "OUT2") (pin "8") (pinfunction "8_8") (pintype "passive+no_connect"))
    )
    (net (code "128") (name "unconnected-(OUT2-Pad9)") (class "Default")
      (node (ref "OUT2") (pin "9") (pinfunction "9_9") (pintype "passive+no_connect"))
    )
    (net (code "129") (name "unconnected-(OUT2-Pad10)") (class "Default")
      (node (ref "OUT2") (pin "10") (pinfunction "10_10") (pintype "passive+no_connect"))
    )
    (net (code "130") (name "unconnected-(OUT2-Pad51)") (class "Default")
      (node (ref "OUT2") (pin "51") (pinfunction "51_51") (pintype "passive+no_connect"))
    )
    (net (code "131") (name "unconnected-(OUT2-Pad52)") (class "Default")
      (node (ref "OUT2") (pin "52") (pinfunction "52_52") (pintype "passive+no_connect"))
    )
    (net (code "132") (name "unconnected-(OUT2-Pad53)") (class "Default")
      (node (ref "OUT2") (pin "53") (pinfunction "53_53") (pintype "passive+no_connect"))
    )
    (net (code "133") (name "unconnected-(OUT2-Pad54)") (class "Default")
      (node (ref "OUT2") (pin "54") (pinfunction "54_54") (pintype "passive+no_connect"))
    )
    (net (code "134") (name "unconnected-(OUT2-Pad55)") (class "Default")
      (node (ref "OUT2") (pin "55") (pinfunction "55_55") (pintype "passive+no_connect"))
    )
    (net (code "135") (name "unconnected-(TEACH_PPM-CHR-Pad2)") (class "Default")
      (node (ref "TEACH_PPM") (pin "2") (pinfunction "CHR_2") (pintype "passive"))
    )
    (net (code "136") (name "unconnected-(U1-AUX_CL-Pad7)") (class "Default")
      (node (ref "U1") (pin "7") (pinfunction "AUX_CL_7") (pintype "passive+no_connect"))
    )
    (net (code "137") (name "unconnected-(U1-AUX_DA-Pad6)") (class "Default")
      (node (ref "U1") (pin "6") (pinfunction "AUX_DA_6") (pintype "passive+no_connect"))
    )
    (net (code "138") (name "unconnected-(U1-NC-Pad2)") (class "Default")
      (node (ref "U1") (pin "2") (pinfunction "NC_2") (pintype "passive+no_connect"))
    )
    (net (code "139") (name "unconnected-(U1-NC-Pad3)") (class "Default")
      (node (ref "U1") (pin "3") (pinfunction "NC_3") (pintype "passive+no_connect"))
    )
    (net (code "140") (name "unconnected-(U1-NC-Pad4)") (class "Default")
      (node (ref "U1") (pin "4") (pinfunction "NC_4") (pintype "passive+no_connect"))
    )
    (net (code "141") (name "unconnected-(U1-NC-Pad5)") (class "Default")
      (node (ref "U1") (pin "5") (pinfunction "NC_5") (pintype "passive+no_connect"))
    )
    (net (code "142") (name "unconnected-(U1-NC-Pad14)") (class "Default")
      (node (ref "U1") (pin "14") (pinfunction "NC_14") (pintype "passive+no_connect"))
    )
    (net (code "143") (name "unconnected-(U1-NC-Pad15)") (class "Default")
      (node (ref "U1") (pin "15") (pinfunction "NC_15") (pintype "passive+no_connect"))
    )
    (net (code "144") (name "unconnected-(U1-NC-Pad16)") (class "Default")
      (node (ref "U1") (pin "16") (pinfunction "NC_16") (pintype "passive+no_connect"))
    )
    (net (code "145") (name "unconnected-(U1-NC-Pad17)") (class "Default")
      (node (ref "U1") (pin "17") (pinfunction "NC_17") (pintype "passive+no_connect"))
    )
    (net (code "146") (name "unconnected-(U1-RESV-Pad19)") (class "Default")
      (node (ref "U1") (pin "19") (pinfunction "RESV_19") (pintype "passive+no_connect"))
    )
    (net (code "147") (name "unconnected-(U1-RESV-Pad21)") (class "Default")
      (node (ref "U1") (pin "21") (pinfunction "RESV_21") (pintype "passive+no_connect"))
    )
    (net (code "148") (name "unconnected-(U1-RESV-Pad22)") (class "Default")
      (node (ref "U1") (pin "22") (pinfunction "RESV_22") (pintype "passive+no_connect"))
    )
  )
)
